# pipower.net
KiCad netlist of a schematic drawn in EAGLE
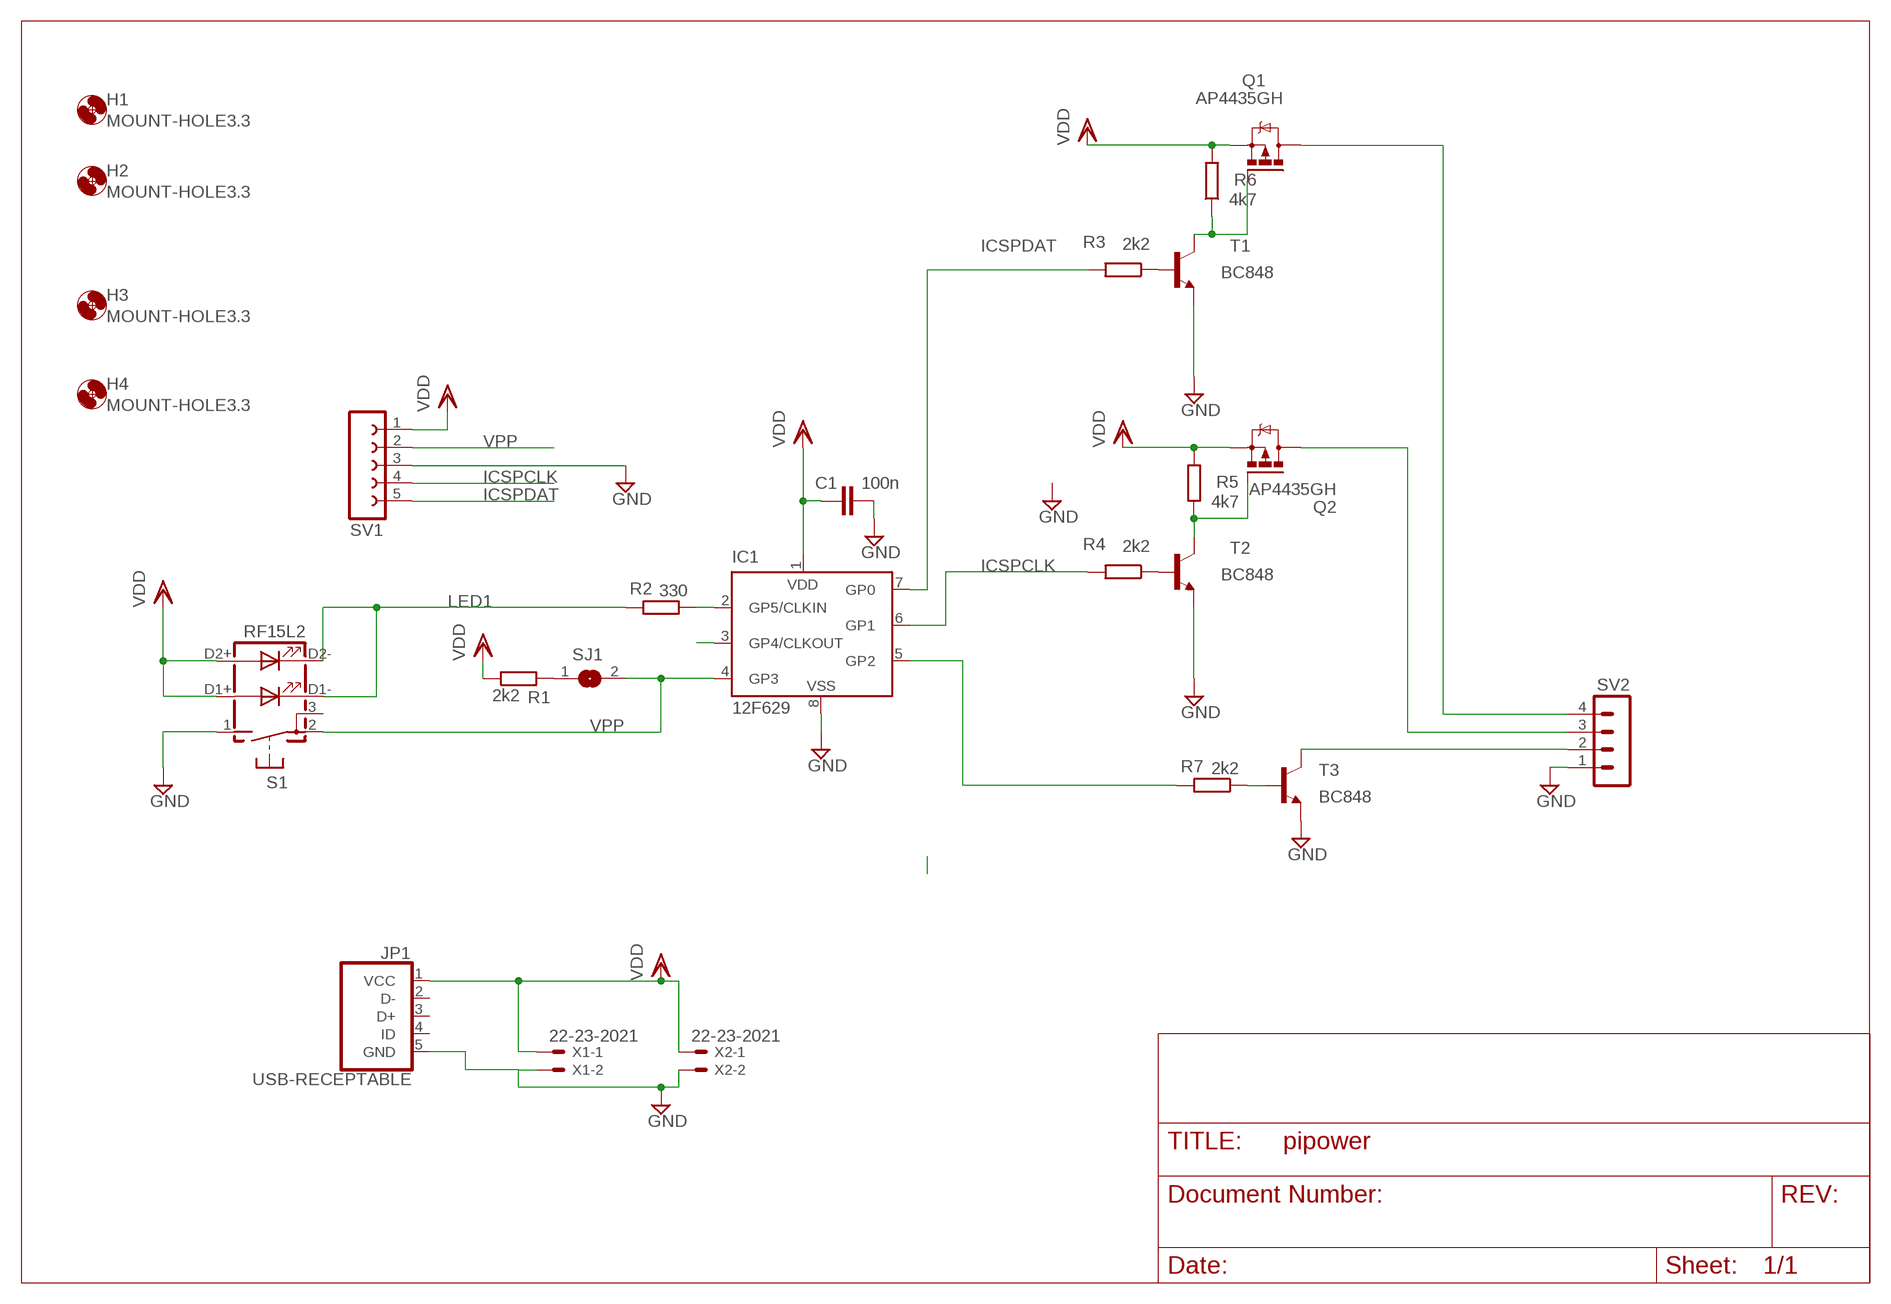
[diagram p0: schematic, sheet 1]

(export (version "E")
  (design (tool "Eeschema 10.0.6"))
  (components
    (comp (ref "C1")
      (value "100n")
      (footprint "eagle-import:C0805")
      (libsource (lib "eagle-import") (part "C-EUC0805"))
    )
    (comp (ref "H1")
      (value "MOUNT-HOLE3.3")
      (footprint "eagle-import:3,3")
      (libsource (lib "eagle-import") (part "MOUNT-HOLE3.3"))
    )
    (comp (ref "H2")
      (value "MOUNT-HOLE3.3")
      (footprint "eagle-import:3,3")
      (libsource (lib "eagle-import") (part "MOUNT-HOLE3.3"))
    )
    (comp (ref "H3")
      (value "MOUNT-HOLE3.3")
      (footprint "eagle-import:3,3")
      (libsource (lib "eagle-import") (part "MOUNT-HOLE3.3"))
    )
    (comp (ref "H4")
      (value "MOUNT-HOLE3.3")
      (footprint "eagle-import:3,3")
      (libsource (lib "eagle-import") (part "MOUNT-HOLE3.3"))
    )
    (comp (ref "IC1")
      (value "12F629")
      (footprint "eagle-import:SO-08")
      (fields
        (field (name "MF") "MICROCHIP")
        (field (name "MPN") "PIC12F629-I/SN")
        (field (name "MPN_1") "PIC12F629-I/SN")
        (field (name "OC_FARNELL") "9759000")
        (field (name "OC_NEWARK") "61K3433")
      )
      (libsource (lib "eagle-import") (part "PIC12F6SN29"))
    )
    (comp (ref "JP1")
      (value "USB-RECEPTABLE")
      (footprint "eagle-import:FCI-10103594-0001LF")
      (libsource (lib "eagle-import") (part "USB-RECEPTABLE"))
    )
    (comp (ref "Q1")
      (value "AP4435GH")
      (footprint "eagle-import:D-PAK_TO252AA")
      (libsource (lib "eagle-import") (part "IRF?5305R"))
    )
    (comp (ref "Q2")
      (value "AP4435GH")
      (footprint "eagle-import:D-PAK_TO252AA")
      (libsource (lib "eagle-import") (part "IRF?5305R"))
    )
    (comp (ref "R1")
      (value "2k2")
      (footprint "eagle-import:R0805")
      (libsource (lib "eagle-import") (part "R-EU_R0805"))
    )
    (comp (ref "R2")
      (value "330")
      (footprint "eagle-import:R0805")
      (libsource (lib "eagle-import") (part "R-EU_R0805"))
    )
    (comp (ref "R3")
      (value "2k2")
      (footprint "eagle-import:R0805")
      (libsource (lib "eagle-import") (part "R-EU_R0805"))
    )
    (comp (ref "R4")
      (value "2k2")
      (footprint "eagle-import:R0805")
      (libsource (lib "eagle-import") (part "R-EU_R0805"))
    )
    (comp (ref "R5")
      (value "4k7")
      (footprint "eagle-import:R0805")
      (libsource (lib "eagle-import") (part "R-EU_R0805"))
    )
    (comp (ref "R6")
      (value "4k7")
      (footprint "eagle-import:R0805")
      (libsource (lib "eagle-import") (part "R-EU_R0805"))
    )
    (comp (ref "R7")
      (value "2k2")
      (footprint "eagle-import:R0805")
      (libsource (lib "eagle-import") (part "R-EU_R0805"))
    )
    (comp (ref "S1")
      (value "RF15L2")
      (footprint "eagle-import:RF15L2")
      (libsource (lib "eagle-import") (part "RF15L2"))
    )
    (comp (ref "SJ1") (value "SJ") (footprint "eagle-import:SJ") (libsource (lib "eagle-import") (part "SJ")))
    (comp (ref "SV1")
      (value "FE05-1")
      (footprint "eagle-import:FE05-1")
      (libsource (lib "eagle-import") (part "FE05-1"))
    )
    (comp (ref "SV2")
      (value "MA04-1")
      (footprint "eagle-import:MA04-1")
      (libsource (lib "eagle-import") (part "MA04-1"))
    )
    (comp (ref "T1")
      (value "BC848")
      (footprint "eagle-import:SOT23")
      (libsource (lib "eagle-import") (part "BC848"))
    )
    (comp (ref "T2")
      (value "BC848")
      (footprint "eagle-import:SOT23")
      (libsource (lib "eagle-import") (part "BC848"))
    )
    (comp (ref "T3")
      (value "BC848")
      (footprint "eagle-import:SOT23")
      (libsource (lib "eagle-import") (part "BC848"))
    )
    (comp (ref "X1")
      (value "22-23-2021")
      (footprint "eagle-import:22-23-2021")
      (fields (field (name "MF") "MOLEX"))
      (libsource (lib "eagle-import") (part "22-23-2021"))
    )
    (comp (ref "X2")
      (value "22-23-2021")
      (footprint "eagle-import:22-23-2021")
      (fields (field (name "MF") "MOLEX"))
      (libsource (lib "eagle-import") (part "22-23-2021"))
    )
  )
  (nets
    (net (code "1") (name "/ICSPCLK") (class "Default")
      (node (ref "IC1") (pin "6") (pinfunction "GP1_6") (pintype "bidirectional"))
      (node (ref "R4") (pin "2") (pinfunction "2_2") (pintype "passive"))
      (node (ref "SV1") (pin "4") (pinfunction "4_4") (pintype "passive"))
    )
    (net (code "2") (name "/ICSPDAT") (class "Default")
      (node (ref "IC1") (pin "7") (pinfunction "GP0_7") (pintype "bidirectional"))
      (node (ref "R3") (pin "2") (pinfunction "2_2") (pintype "passive"))
      (node (ref "SV1") (pin "5") (pinfunction "5_5") (pintype "passive"))
    )
    (net (code "3") (name "/LED1") (class "Default")
      (node (ref "R2") (pin "2") (pinfunction "2_2") (pintype "passive"))
      (node (ref "S1") (pin "D1-") (pinfunction "C1_D1-") (pintype "passive"))
      (node (ref "S1") (pin "D2-") (pinfunction "C2_D2-") (pintype "passive"))
    )
    (net (code "4") (name "/VPP") (class "Default")
      (node (ref "IC1") (pin "4") (pinfunction "GP3_4") (pintype "input"))
      (node (ref "S1") (pin "2") (pinfunction "P_2") (pintype "passive"))
      (node (ref "SJ1") (pin "2") (pinfunction "2_2") (pintype "passive"))
      (node (ref "SV1") (pin "2") (pinfunction "2_2") (pintype "passive"))
    )
    (net (code "5") (name "GND") (class "Default")
      (node (ref "C1") (pin "2") (pinfunction "2_2") (pintype "passive"))
      (node (ref "IC1") (pin "8") (pinfunction "VSS_8") (pintype "power_in"))
      (node (ref "JP1") (pin "5") (pinfunction "GND_5") (pintype "bidirectional"))
      (node (ref "S1") (pin "1") (pinfunction "S_1") (pintype "passive"))
      (node (ref "SV1") (pin "3") (pinfunction "3_3") (pintype "passive"))
      (node (ref "SV2") (pin "1") (pinfunction "1_1") (pintype "passive"))
      (node (ref "T1") (pin "2") (pinfunction "E_2") (pintype "passive"))
      (node (ref "T2") (pin "2") (pinfunction "E_2") (pintype "passive"))
      (node (ref "T3") (pin "2") (pinfunction "E_2") (pintype "passive"))
      (node (ref "X1") (pin "2") (pinfunction "S_2") (pintype "passive"))
      (node (ref "X2") (pin "2") (pinfunction "S_2") (pintype "passive"))
    )
    (net (code "6") (name "Net-(IC1-GP2)") (class "Default")
      (node (ref "IC1") (pin "5") (pinfunction "GP2_5") (pintype "bidirectional"))
      (node (ref "R7") (pin "2") (pinfunction "2_2") (pintype "passive"))
    )
    (net (code "7") (name "Net-(IC1-GP5{slash}CLKIN)") (class "Default")
      (node (ref "IC1") (pin "2") (pinfunction "GP5/CLKIN_2") (pintype "bidirectional"))
      (node (ref "R2") (pin "1") (pinfunction "1_1") (pintype "passive"))
    )
    (net (code "8") (name "Net-(Q1-D)") (class "Default")
      (node (ref "Q1") (pin "4") (pinfunction "D_4") (pintype "passive"))
      (node (ref "SV2") (pin "4") (pinfunction "4_4") (pintype "passive"))
    )
    (net (code "9") (name "Net-(Q1-G)") (class "Default")
      (node (ref "Q1") (pin "1") (pinfunction "G_1") (pintype "passive"))
      (node (ref "R6") (pin "1") (pinfunction "1_1") (pintype "passive"))
      (node (ref "T1") (pin "3") (pinfunction "C_3") (pintype "passive"))
    )
    (net (code "10") (name "Net-(Q2-D)") (class "Default")
      (node (ref "Q2") (pin "4") (pinfunction "D_4") (pintype "passive"))
      (node (ref "SV2") (pin "3") (pinfunction "3_3") (pintype "passive"))
    )
    (net (code "11") (name "Net-(Q2-G)") (class "Default")
      (node (ref "Q2") (pin "1") (pinfunction "G_1") (pintype "passive"))
      (node (ref "R5") (pin "1") (pinfunction "1_1") (pintype "passive"))
      (node (ref "T2") (pin "3") (pinfunction "C_3") (pintype "passive"))
    )
    (net (code "12") (name "Net-(R1-Pad2)") (class "Default")
      (node (ref "R1") (pin "2") (pinfunction "2_2") (pintype "passive"))
      (node (ref "SJ1") (pin "1") (pinfunction "1_1") (pintype "passive"))
    )
    (net (code "13") (name "Net-(T1-B)") (class "Default")
      (node (ref "R3") (pin "1") (pinfunction "1_1") (pintype "passive"))
      (node (ref "T1") (pin "1") (pinfunction "B_1") (pintype "passive"))
    )
    (net (code "14") (name "Net-(T2-B)") (class "Default")
      (node (ref "R4") (pin "1") (pinfunction "1_1") (pintype "passive"))
      (node (ref "T2") (pin "1") (pinfunction "B_1") (pintype "passive"))
    )
    (net (code "15") (name "Net-(T3-B)") (class "Default")
      (node (ref "R7") (pin "1") (pinfunction "1_1") (pintype "passive"))
      (node (ref "T3") (pin "1") (pinfunction "B_1") (pintype "passive"))
    )
    (net (code "16") (name "Net-(T3-C)") (class "Default")
      (node (ref "SV2") (pin "2") (pinfunction "2_2") (pintype "passive"))
      (node (ref "T3") (pin "3") (pinfunction "C_3") (pintype "passive"))
    )
    (net (code "17") (name "VDD") (class "Default")
      (node (ref "C1") (pin "1") (pinfunction "1_1") (pintype "passive"))
      (node (ref "IC1") (pin "1") (pinfunction "VDD_1") (pintype "power_in"))
      (node (ref "JP1") (pin "1") (pinfunction "VCC_1") (pintype "bidirectional"))
      (node (ref "Q1") (pin "3") (pinfunction "S_3") (pintype "passive"))
      (node (ref "Q2") (pin "3") (pinfunction "S_3") (pintype "passive"))
      (node (ref "R1") (pin "1") (pinfunction "1_1") (pintype "passive"))
      (node (ref "R5") (pin "2") (pinfunction "2_2") (pintype "passive"))
      (node (ref "R6") (pin "2") (pinfunction "2_2") (pintype "passive"))
      (node (ref "S1") (pin "D1+") (pinfunction "A1_D1+") (pintype "passive"))
      (node (ref "S1") (pin "D2+") (pinfunction "A2_D2+") (pintype "passive"))
      (node (ref "SV1") (pin "1") (pinfunction "1_1") (pintype "passive"))
      (node (ref "X1") (pin "1") (pinfunction "S_1") (pintype "passive"))
      (node (ref "X2") (pin "1") (pinfunction "S_1") (pintype "passive"))
    )
    (net (code "18") (name "unconnected-(IC1-GP4{slash}CLKOUT-Pad3)") (class "Default")
      (node (ref "IC1") (pin "3") (pinfunction "GP4/CLKOUT_3") (pintype "bidirectional"))
    )
    (net (code "19") (name "unconnected-(JP1-D+-Pad3)") (class "Default")
      (node (ref "JP1") (pin "3") (pinfunction "D+_3") (pintype "bidirectional"))
    )
    (net (code "20") (name "unconnected-(JP1-D--Pad2)") (class "Default")
      (node (ref "JP1") (pin "2") (pinfunction "D-_2") (pintype "bidirectional"))
    )
    (net (code "21") (name "unconnected-(JP1-ID-Pad4)") (class "Default")
      (node (ref "JP1") (pin "4") (pinfunction "ID_4") (pintype "bidirectional"))
    )
    (net (code "22") (name "unconnected-(S1-P-Pad3)") (class "Default")
      (node (ref "S1") (pin "3") (pinfunction "P_3") (pintype "passive"))
    )
  )
)
